# MCU.net
KiCad netlist of a schematic drawn in Altium Designer
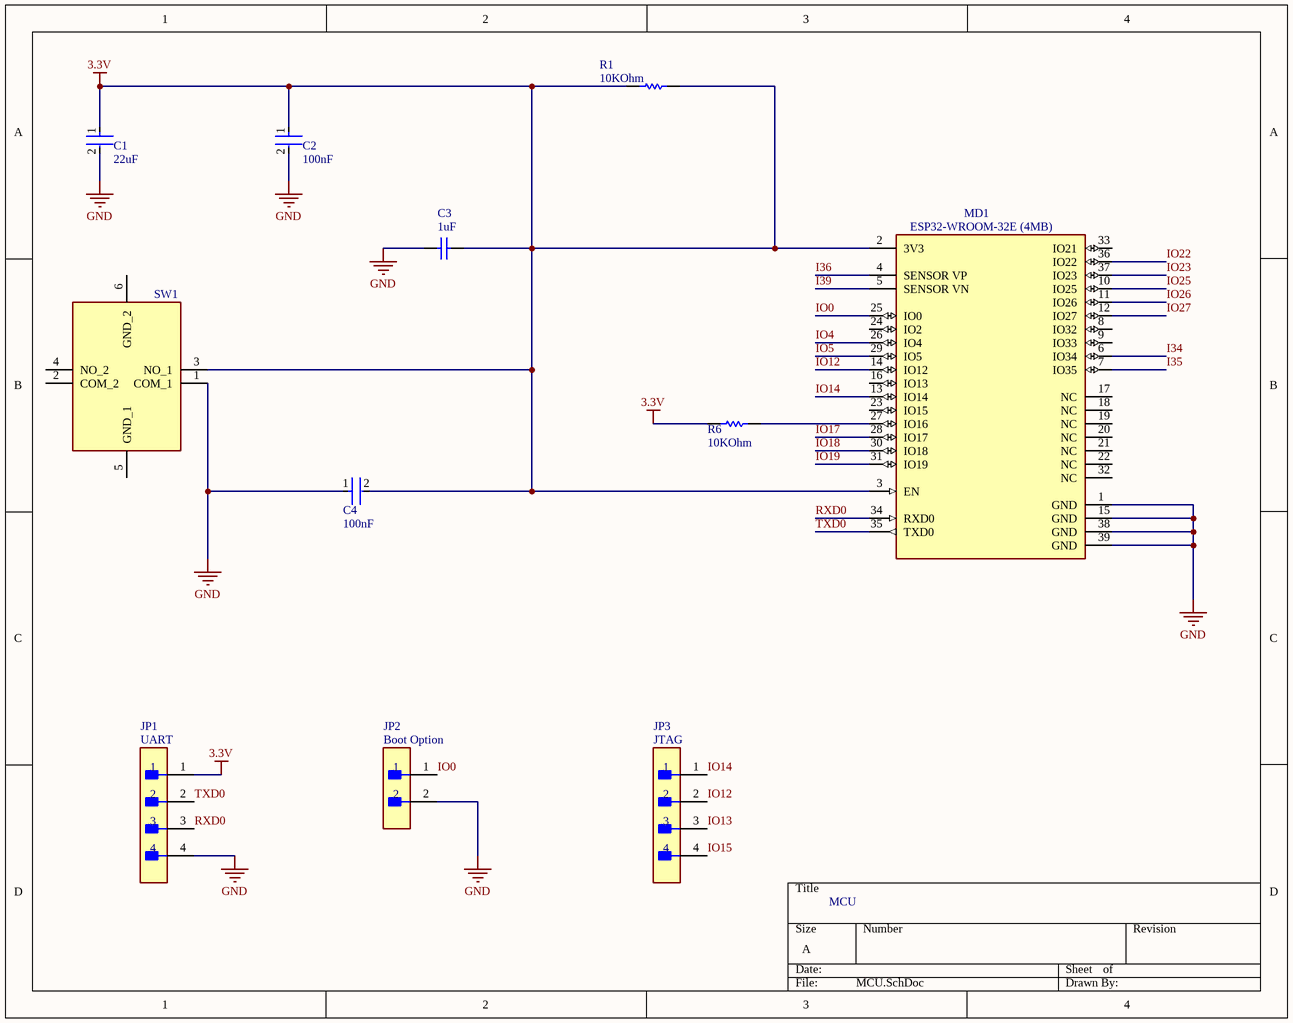
[diagram p0: MCU.SchDoc]

(export (version "E")
  (design (tool "Eeschema 10.0.6"))
  (components
    (comp (ref "C1")
      (value "GRM21BR60J226ME39L")
      (footprint "FP-GRM21B-0_15-MFG")
      (description "Chip Multilayer Ceramic Capacitors for General Purpose, 0805, 22uF, X5R, 15%, 20%, 6.3V")
      (fields
        (field (name "VOLTAGE") "6.3V")
        (field (name "TOLERANCE") "20%")
        (field (name "CAPACITANCE") "22uF")
      )
      (libsource (lib "Altium Content Vault") (part "b4654b650e69147ec39a6b967a45e02"))
    )
    (comp (ref "C2")
      (value "GRM033R61A104KE15D")
      (footprint "FP-GRM033-0_03-IPC_C")
      (description "Chip Multilayer Ceramic Capacitors for General Purpose, 0201, 0.10uF, X5R, 15%, 10%, 10V")
      (fields
        (field (name "TOLERANCE") "10%")
        (field (name "CAPACITANCE") "100nF")
        (field (name "VOLTAGE") "10V")
      )
      (libsource (lib "Altium Content Vault") (part "b4654b650e69147ec39a6b967a45e02"))
    )
    (comp (ref "C3")
      (value "C0805C105K4PACTU")
      (footprint "CAPC2013X145X50LL20T25")
      (fields (field (name "MANUFACTURER") "Kemet") (field (name "CAPACITANCE") "1uF"))
      (libsource (lib "Altium Content Vault") (part "CAP"))
    )
    (comp (ref "C4")
      (value "GRM033R61A104KE15D")
      (footprint "FP-GRM033-0_03-IPC_C")
      (description "Chip Multilayer Ceramic Capacitors for General Purpose, 0201, 0.10uF, X5R, 15%, 10%, 10V")
      (fields
        (field (name "TOLERANCE") "10%")
        (field (name "CAPACITANCE") "100nF")
        (field (name "VOLTAGE") "10V")
      )
      (libsource (lib "Altium Content Vault") (part "b4654b650e69147ec39a6b967a45e02"))
    )
    (comp (ref "JP1")
      (value "B4B-XH-A(LF)(SN)")
      (footprint "FP-B4B-XH-A_LF_SN-MFG")
      (description "CONN HEADER VERT 4POS 2.5MM")
      (fields (field (name "PURPOSE") "UART"))
      (libsource (lib "Altium Content Vault") (part "299a8cea1bdcbc3624fe62c390fa72c"))
    )
    (comp (ref "JP2")
      (value "B2B-XH-A(LF)(SN)")
      (footprint "FP-B2B-XH-A_LF_SN-MFG")
      (description "CONN HEADER VERT 2POS 2.5MM")
      (fields (field (name "PURPOSE") "Boot Option"))
      (libsource (lib "Altium Content Vault") (part "3bc925449376181038e59eaffc5286c"))
    )
    (comp (ref "JP3")
      (value "B4B-XH-A(LF)(SN)")
      (footprint "FP-B4B-XH-A_LF_SN-MFG")
      (description "CONN HEADER VERT 4POS 2.5MM")
      (fields (field (name "PURPOSE") "JTAG"))
      (libsource (lib "Altium Content Vault") (part "299a8cea1bdcbc3624fe62c390fa72c"))
    )
    (comp (ref "MD1")
      (value "ESP32-WROOM-32E (4MB)")
      (footprint "FP-ESP32-WROOM-32E_4MB-MFG")
      (description "RX TXRX MOD WIFI TRACE ANT SMD")
      (libsource (lib "Altium Content Vault") (part "7f842c3463a9561e2f6f9fdcd687e0f"))
    )
    (comp (ref "R1")
      (value "ERJ2RKF1002X")
      (footprint "RESC1005X40X25LL05T05")
      (description "Chip Resistor, 10 KOhm, +/- 1%, 0.1 W, -55 to 155 degC, 0402 (1005 Metric), RoHS, Tape and Reel")
      (fields
        (field (name "RESISTANCE") "10KOhm")
        (field (name "TOLERANCE") "1%")
        (field (name "MANUFACTURER") "Panasonic")
      )
      (libsource (lib "Altium Content Vault") (part "RES-2"))
    )
    (comp (ref "R6")
      (value "ERJ2RKF1002X")
      (footprint "RESC1005X40X25LL05T05")
      (description "Chip Resistor, 10 KOhm, +/- 1%, 0.1 W, -55 to 155 degC, 0402 (1005 Metric), RoHS, Tape and Reel")
      (fields
        (field (name "RESISTANCE") "10KOhm")
        (field (name "TOLERANCE") "1%")
        (field (name "MANUFACTURER") "Panasonic")
      )
      (libsource (lib "Altium Content Vault") (part "RES-2"))
    )
    (comp (ref "SW1")
      (value "PTS526SMG20SMTR21_LFS")
      (footprint "SamacSys:PTS526SMG20SMTR21LFS")
      (description "Switch")
      (fields
        (field (name "MANUFACTURER_PART_NUMBER") "PTS526SMG20SMTR21 LFS")
        (field (name "MOUSER PART NUMBER") "611-PTS526SMG20S21LF")
      )
      (libsource (lib "*") (part "PTS526SMG20SMTR21_LFS"))
    )
  )
  (nets
    (net (code "1") (name "/I34") (class "Default")
      (node (ref "MD1") (pin "6") (pinfunction "IO34_6") (pintype "bidirectional"))
    )
    (net (code "2") (name "/I35") (class "Default")
      (node (ref "MD1") (pin "7") (pinfunction "IO35_7") (pintype "bidirectional"))
    )
    (net (code "3") (name "/I36") (class "Default")
      (node (ref "MD1") (pin "4") (pinfunction "SENSOR_VP_4") (pintype "passive"))
    )
    (net (code "4") (name "/I39") (class "Default")
      (node (ref "MD1") (pin "5") (pinfunction "SENSOR_VN_5") (pintype "passive"))
    )
    (net (code "5") (name "/IO0") (class "Default")
      (node (ref "JP2") (pin "1") (pinfunction "1_1") (pintype "passive"))
      (node (ref "MD1") (pin "25") (pinfunction "IO0_25") (pintype "bidirectional"))
    )
    (net (code "6") (name "/IO4") (class "Default")
      (node (ref "MD1") (pin "26") (pinfunction "IO4_26") (pintype "bidirectional"))
    )
    (net (code "7") (name "/IO5") (class "Default")
      (node (ref "MD1") (pin "29") (pinfunction "IO5_29") (pintype "bidirectional"))
    )
    (net (code "8") (name "/IO12") (class "Default")
      (node (ref "JP3") (pin "2") (pinfunction "2_2") (pintype "passive"))
      (node (ref "MD1") (pin "14") (pinfunction "IO12_14") (pintype "bidirectional"))
    )
    (net (code "9") (name "/IO13") (class "Default")
      (node (ref "JP3") (pin "3") (pinfunction "3_3") (pintype "passive"))
    )
    (net (code "10") (name "/IO14") (class "Default")
      (node (ref "JP3") (pin "1") (pinfunction "1_1") (pintype "passive"))
      (node (ref "MD1") (pin "13") (pinfunction "IO14_13") (pintype "bidirectional"))
    )
    (net (code "11") (name "/IO15") (class "Default")
      (node (ref "JP3") (pin "4") (pinfunction "4_4") (pintype "passive"))
    )
    (net (code "12") (name "/IO17") (class "Default")
      (node (ref "MD1") (pin "28") (pinfunction "IO17_28") (pintype "bidirectional"))
    )
    (net (code "13") (name "/IO18") (class "Default")
      (node (ref "MD1") (pin "30") (pinfunction "IO18_30") (pintype "bidirectional"))
    )
    (net (code "14") (name "/IO19") (class "Default")
      (node (ref "MD1") (pin "31") (pinfunction "IO19_31") (pintype "bidirectional"))
    )
    (net (code "15") (name "/IO22") (class "Default")
      (node (ref "MD1") (pin "36") (pinfunction "IO22_36") (pintype "bidirectional"))
    )
    (net (code "16") (name "/IO23") (class "Default")
      (node (ref "MD1") (pin "37") (pinfunction "IO23_37") (pintype "bidirectional"))
    )
    (net (code "17") (name "/IO25") (class "Default")
      (node (ref "MD1") (pin "10") (pinfunction "IO25_10") (pintype "bidirectional"))
    )
    (net (code "18") (name "/IO26") (class "Default")
      (node (ref "MD1") (pin "11") (pinfunction "IO26_11") (pintype "bidirectional"))
    )
    (net (code "19") (name "/IO27") (class "Default")
      (node (ref "MD1") (pin "12") (pinfunction "IO27_12") (pintype "bidirectional"))
    )
    (net (code "20") (name "/RXD0") (class "Default")
      (node (ref "JP1") (pin "3") (pinfunction "3_3") (pintype "passive"))
      (node (ref "MD1") (pin "34") (pinfunction "RXD0_34") (pintype "input"))
    )
    (net (code "21") (name "/TXD0") (class "Default")
      (node (ref "JP1") (pin "2") (pinfunction "2_2") (pintype "passive"))
      (node (ref "MD1") (pin "35") (pinfunction "TXD0_35") (pintype "output"))
    )
    (net (code "22") (name "3.3V") (class "Default")
      (node (ref "C1") (pin "1") (pinfunction "1_1") (pintype "passive"))
      (node (ref "C2") (pin "1") (pinfunction "1_1") (pintype "passive"))
      (node (ref "C3") (pin "2") (pinfunction "2_2") (pintype "passive"))
      (node (ref "C4") (pin "2") (pinfunction "2_2") (pintype "passive"))
      (node (ref "JP1") (pin "1") (pinfunction "1_1") (pintype "passive"))
      (node (ref "MD1") (pin "2") (pinfunction "3V3_2") (pintype "power_in"))
      (node (ref "MD1") (pin "3") (pinfunction "EN_3") (pintype "input"))
      (node (ref "R1") (pin "1") (pinfunction "1_1") (pintype "passive"))
      (node (ref "R1") (pin "2") (pinfunction "2_2") (pintype "passive"))
      (node (ref "R6") (pin "1") (pinfunction "1_1") (pintype "passive"))
      (node (ref "SW1") (pin "3") (pinfunction "NO_1_3") (pintype "passive"))
    )
    (net (code "23") (name "GND") (class "Default")
      (node (ref "C1") (pin "2") (pinfunction "2_2") (pintype "passive"))
      (node (ref "C2") (pin "2") (pinfunction "2_2") (pintype "passive"))
      (node (ref "C3") (pin "1") (pinfunction "1_1") (pintype "passive"))
      (node (ref "C4") (pin "1") (pinfunction "1_1") (pintype "passive"))
      (node (ref "JP1") (pin "4") (pinfunction "4_4") (pintype "passive"))
      (node (ref "JP2") (pin "2") (pinfunction "2_2") (pintype "passive"))
      (node (ref "MD1") (pin "1") (pinfunction "GND_1") (pintype "power_in"))
      (node (ref "MD1") (pin "15") (pinfunction "GND_15") (pintype "power_in"))
      (node (ref "MD1") (pin "38") (pinfunction "GND_38") (pintype "power_in"))
      (node (ref "MD1") (pin "39") (pinfunction "GND_39") (pintype "power_in"))
      (node (ref "SW1") (pin "1") (pinfunction "COM_1_1") (pintype "passive"))
    )
    (net (code "24") (name "Net-(MD1-IO16)") (class "Default")
      (node (ref "MD1") (pin "27") (pinfunction "IO16_27") (pintype "bidirectional"))
      (node (ref "R6") (pin "2") (pinfunction "2_2") (pintype "passive"))
    )
    (net (code "25") (name "unconnected-(MD1-IO2-Pad24)") (class "Default")
      (node (ref "MD1") (pin "24") (pinfunction "IO2_24") (pintype "bidirectional"))
    )
    (net (code "26") (name "unconnected-(MD1-IO13-Pad16)") (class "Default")
      (node (ref "MD1") (pin "16") (pinfunction "IO13_16") (pintype "bidirectional"))
    )
    (net (code "27") (name "unconnected-(MD1-IO15-Pad23)") (class "Default")
      (node (ref "MD1") (pin "23") (pinfunction "IO15_23") (pintype "bidirectional"))
    )
    (net (code "28") (name "unconnected-(MD1-IO21-Pad33)") (class "Default")
      (node (ref "MD1") (pin "33") (pinfunction "IO21_33") (pintype "bidirectional"))
    )
    (net (code "29") (name "unconnected-(MD1-IO32-Pad8)") (class "Default")
      (node (ref "MD1") (pin "8") (pinfunction "IO32_8") (pintype "bidirectional"))
    )
    (net (code "30") (name "unconnected-(MD1-IO33-Pad9)") (class "Default")
      (node (ref "MD1") (pin "9") (pinfunction "IO33_9") (pintype "bidirectional"))
    )
    (net (code "31") (name "unconnected-(MD1-NC-Pad17)") (class "Default")
      (node (ref "MD1") (pin "17") (pinfunction "NC_17") (pintype "passive"))
    )
    (net (code "32") (name "unconnected-(MD1-NC-Pad18)") (class "Default")
      (node (ref "MD1") (pin "18") (pinfunction "NC_18") (pintype "passive"))
    )
    (net (code "33") (name "unconnected-(MD1-NC-Pad19)") (class "Default")
      (node (ref "MD1") (pin "19") (pinfunction "NC_19") (pintype "passive"))
    )
    (net (code "34") (name "unconnected-(MD1-NC-Pad20)") (class "Default")
      (node (ref "MD1") (pin "20") (pinfunction "NC_20") (pintype "passive"))
    )
    (net (code "35") (name "unconnected-(MD1-NC-Pad21)") (class "Default")
      (node (ref "MD1") (pin "21") (pinfunction "NC_21") (pintype "passive"))
    )
    (net (code "36") (name "unconnected-(MD1-NC-Pad22)") (class "Default")
      (node (ref "MD1") (pin "22") (pinfunction "NC_22") (pintype "passive"))
    )
    (net (code "37") (name "unconnected-(MD1-NC-Pad32)") (class "Default")
      (node (ref "MD1") (pin "32") (pinfunction "NC_32") (pintype "passive"))
    )
    (net (code "38") (name "unconnected-(SW1-COM_2-Pad2)") (class "Default")
      (node (ref "SW1") (pin "2") (pinfunction "COM_2_2") (pintype "passive"))
    )
    (net (code "39") (name "unconnected-(SW1-GND_1-Pad5)") (class "Default")
      (node (ref "SW1") (pin "5") (pinfunction "GND_1_5") (pintype "passive"))
    )
    (net (code "40") (name "unconnected-(SW1-GND_2-Pad6)") (class "Default")
      (node (ref "SW1") (pin "6") (pinfunction "GND_2_6") (pintype "passive"))
    )
    (net (code "41") (name "unconnected-(SW1-NO_2-Pad4)") (class "Default")
      (node (ref "SW1") (pin "4") (pinfunction "NO_2_4") (pintype "passive"))
    )
  )
)
